# DS1307_Rev_B.net
KiCad netlist of a schematic drawn in EAGLE
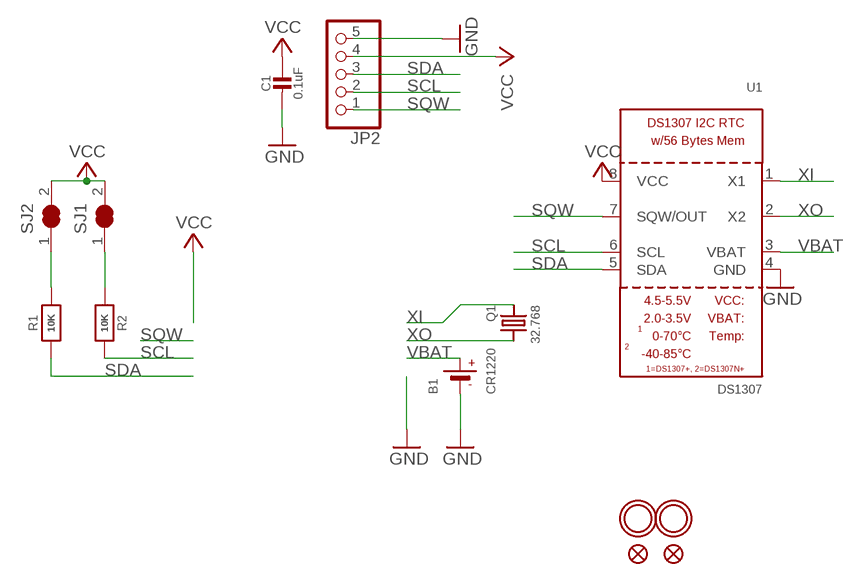
[diagram p0: schematic, sheet 1]

(export (version "E")
  (design (tool "Eeschema 10.0.6"))
  (components
    (comp (ref "B1")
      (value "CR1220")
      (footprint "eagle-import:CR1220")
      (libsource (lib "eagle-import") (part "BATTERYCR1220_SMT"))
    )
    (comp (ref "C1")
      (value "0.1uF")
      (footprint "eagle-import:0805-NO")
      (libsource (lib "eagle-import") (part "CAP_CERAMIC0805-NOOUTLINE"))
    )
    (comp (ref "FID1")
      (value "FIDUCIAL\"\"")
      (footprint "eagle-import:FIDUCIAL_1MM")
      (libsource (lib "eagle-import") (part "FIDUCIAL{dblquote}{dblquote}"))
    )
    (comp (ref "FID2")
      (value "FIDUCIAL\"\"")
      (footprint "eagle-import:FIDUCIAL_1MM")
      (libsource (lib "eagle-import") (part "FIDUCIAL{dblquote}{dblquote}"))
    )
    (comp (ref "JP2")
      (value "HEADER-1X576MIL")
      (footprint "eagle-import:1X05_ROUND_76")
      (libsource (lib "eagle-import") (part "HEADER-1X576MIL"))
    )
    (comp (ref "Q1")
      (value "32.768")
      (footprint "eagle-import:CRYSTAL_8X3.8")
      (libsource (lib "eagle-import") (part "CRYSTAL8.0X3.8"))
    )
    (comp (ref "R1")
      (value "10K")
      (footprint "eagle-import:0805-NO")
      (libsource (lib "eagle-import") (part "RESISTOR0805_NOOUTLINE"))
    )
    (comp (ref "R2")
      (value "10K")
      (footprint "eagle-import:0805-NO")
      (libsource (lib "eagle-import") (part "RESISTOR0805_NOOUTLINE"))
    )
    (comp (ref "SJ1")
      (value "SOLDERJUMPER_CLOSED")
      (footprint "eagle-import:SOLDERJUMPER_CLOSEDWIRE")
      (libsource (lib "eagle-import") (part "SOLDERJUMPER_CLOSED"))
    )
    (comp (ref "SJ2")
      (value "SOLDERJUMPER_CLOSED")
      (footprint "eagle-import:SOLDERJUMPER_CLOSEDWIRE")
      (libsource (lib "eagle-import") (part "SOLDERJUMPER_CLOSED"))
    )
    (comp (ref "U$1")
      (value "MOUNTINGHOLE2.0")
      (footprint "eagle-import:MOUNTINGHOLE_2.0_PLATED")
      (libsource (lib "eagle-import") (part "MOUNTINGHOLE2.0"))
    )
    (comp (ref "U$4")
      (value "MOUNTINGHOLE2.0")
      (footprint "eagle-import:MOUNTINGHOLE_2.0_PLATED")
      (libsource (lib "eagle-import") (part "MOUNTINGHOLE2.0"))
    )
    (comp (ref "U1")
      (value "DS1307")
      (footprint "eagle-import:SOIC8_150MIL")
      (libsource (lib "eagle-import") (part "RTC_DS1307"))
    )
  )
  (nets
    (net (code "1") (name "/SCL") (class "Default")
      (node (ref "JP2") (pin "2") (pinfunction "2_2") (pintype "passive"))
      (node (ref "R2") (pin "2") (pinfunction "2_2") (pintype "passive"))
      (node (ref "U1") (pin "6") (pinfunction "SCL_6") (pintype "bidirectional"))
    )
    (net (code "2") (name "/SDA") (class "Default")
      (node (ref "JP2") (pin "3") (pinfunction "3_3") (pintype "passive"))
      (node (ref "R1") (pin "1") (pinfunction "1_1") (pintype "passive"))
      (node (ref "U1") (pin "5") (pinfunction "SDA_5") (pintype "bidirectional"))
    )
    (net (code "3") (name "/SQW") (class "Default")
      (node (ref "JP2") (pin "1") (pinfunction "1_1") (pintype "passive"))
      (node (ref "U1") (pin "7") (pinfunction "SQW/OUT_7") (pintype "bidirectional"))
    )
    (net (code "4") (name "/VBAT") (class "Default")
      (node (ref "B1") (pin "+$1") (pinfunction "+_+$1") (pintype "passive"))
      (node (ref "U1") (pin "3") (pinfunction "VBAT_3") (pintype "bidirectional"))
    )
    (net (code "5") (name "/XI") (class "Default")
      (node (ref "Q1") (pin "P$1") (pinfunction "1_P$1") (pintype "passive"))
      (node (ref "U1") (pin "1") (pinfunction "X1_1") (pintype "bidirectional"))
    )
    (net (code "6") (name "/XO") (class "Default")
      (node (ref "Q1") (pin "P$4") (pinfunction "2_P$4") (pintype "passive"))
      (node (ref "U1") (pin "2") (pinfunction "X2_2") (pintype "bidirectional"))
    )
    (net (code "7") (name "GND") (class "Default")
      (node (ref "B1") (pin "-") (pinfunction "-_-") (pintype "passive"))
      (node (ref "C1") (pin "2") (pinfunction "2_2") (pintype "passive"))
      (node (ref "JP2") (pin "5") (pinfunction "5_5") (pintype "passive"))
      (node (ref "U1") (pin "4") (pinfunction "GND_4") (pintype "bidirectional"))
    )
    (net (code "8") (name "Net-(R1-Pad2)") (class "Default")
      (node (ref "R1") (pin "2") (pinfunction "2_2") (pintype "passive"))
      (node (ref "SJ2") (pin "1") (pinfunction "1_1") (pintype "passive"))
    )
    (net (code "9") (name "Net-(R2-Pad1)") (class "Default")
      (node (ref "R2") (pin "1") (pinfunction "1_1") (pintype "passive"))
      (node (ref "SJ1") (pin "1") (pinfunction "1_1") (pintype "passive"))
    )
    (net (code "10") (name "VCC") (class "Default")
      (node (ref "C1") (pin "1") (pinfunction "1_1") (pintype "passive"))
      (node (ref "JP2") (pin "4") (pinfunction "4_4") (pintype "passive"))
      (node (ref "SJ1") (pin "2") (pinfunction "2_2") (pintype "passive"))
      (node (ref "SJ2") (pin "2") (pinfunction "2_2") (pintype "passive"))
      (node (ref "U1") (pin "8") (pinfunction "VCC_8") (pintype "bidirectional"))
    )
  )
)
